# Power_Supply.net
KiCad netlist of a schematic drawn in Altium Designer
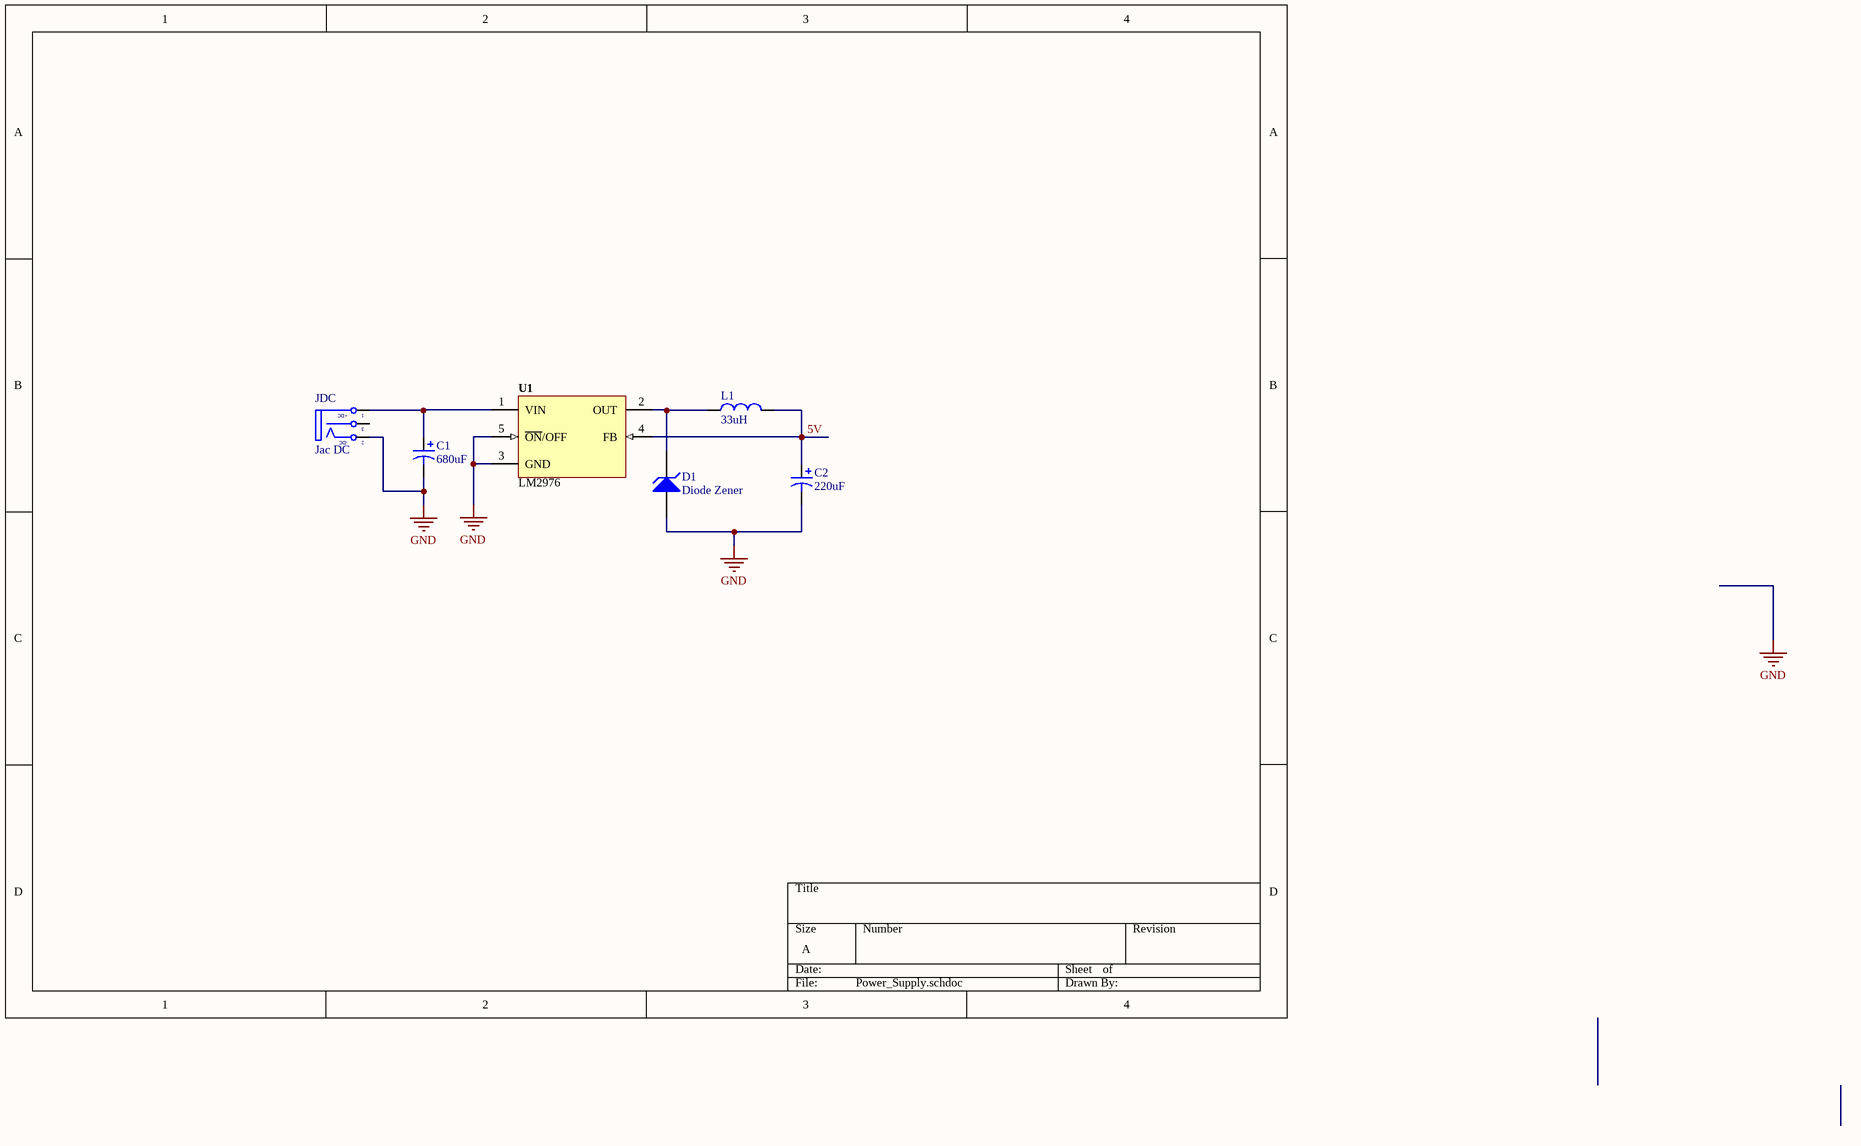
[diagram p0: Power_Supply.schdoc]

(export (version "E")
  (design (tool "Eeschema 10.0.6"))
  (components
    (comp (ref "C1")
      (value "680uF")
      (footprint "C5mm")
      (description "Polarized Capacitor (Axial)")
      (fields (field (name "PUBLISHER") "Altium Limited"))
      (libsource (lib "My Library") (part "Cap Pol 5mm"))
    )
    (comp (ref "C2")
      (value "220uF")
      (footprint "C5mm")
      (description "Polarized Capacitor (Axial)")
      (fields (field (name "PUBLISHER") "Altium Limited"))
      (libsource (lib "My Library") (part "Cap Pol 5mm"))
    )
    (comp (ref "D1")
      (value "Diode Zener")
      (footprint "SMA")
      (description "Zener Diode")
      (fields (field (name "PUBLISHER") "Altium Limited"))
      (libsource (lib "My Library") (part "Diode Zener"))
    )
    (comp (ref "JDC")
      (value "Jac DC")
      (footprint "DC0")
      (description "Jac DC input")
      (libsource (lib "LIBRARY1") (part "DCIN"))
    )
    (comp (ref "L1")
      (value "33uH")
      (footprint "My Library:L-SMD-M-7.3x4.5")
      (description "Inductor")
      (libsource (lib "My Library") (part "L1"))
    )
    (comp (ref "U1") (value "LM2976") (footprint "TO263") (libsource (lib "My Library") (part "LM2596")))
  )
  (nets
    (net (code "1") (name "/5V") (class "Default")
      (node (ref "C2") (pin "1") (pinfunction "1_1") (pintype "passive"))
      (node (ref "L1") (pin "2") (pinfunction "2_2") (pintype "passive"))
      (node (ref "U1") (pin "4") (pinfunction "FB_4") (pintype "input"))
    )
    (net (code "2") (name "GND") (class "Default")
      (node (ref "C1") (pin "2") (pinfunction "2_2") (pintype "passive"))
      (node (ref "C2") (pin "2") (pinfunction "2_2") (pintype "passive"))
      (node (ref "D1") (pin "1") (pinfunction "A_1") (pintype "passive"))
      (node (ref "JDC") (pin "2") (pinfunction "TN_2") (pintype "passive"))
      (node (ref "U1") (pin "3") (pinfunction "GND_3") (pintype "power_in"))
      (node (ref "U1") (pin "5") (pinfunction "~{ON}/OFF_5") (pintype "input"))
    )
    (net (code "3") (name "Net-(D1-K)") (class "Default")
      (node (ref "D1") (pin "2") (pinfunction "K_2") (pintype "passive"))
      (node (ref "L1") (pin "1") (pinfunction "1_1") (pintype "passive"))
      (node (ref "U1") (pin "2") (pinfunction "OUT_2") (pintype "power_in"))
    )
    (net (code "4") (name "Net-(JDC-T)") (class "Default")
      (node (ref "C1") (pin "1") (pinfunction "1_1") (pintype "passive"))
      (node (ref "JDC") (pin "1") (pinfunction "T_1") (pintype "passive"))
      (node (ref "U1") (pin "1") (pinfunction "VIN_1") (pintype "power_in"))
    )
    (net (code "5") (name "unconnected-(JDC-S-Pad3)") (class "Default")
      (node (ref "JDC") (pin "3") (pinfunction "S_3") (pintype "power_in"))
    )
  )
)
